# powerSupply.net
KiCad netlist of a schematic drawn in Altium Designer
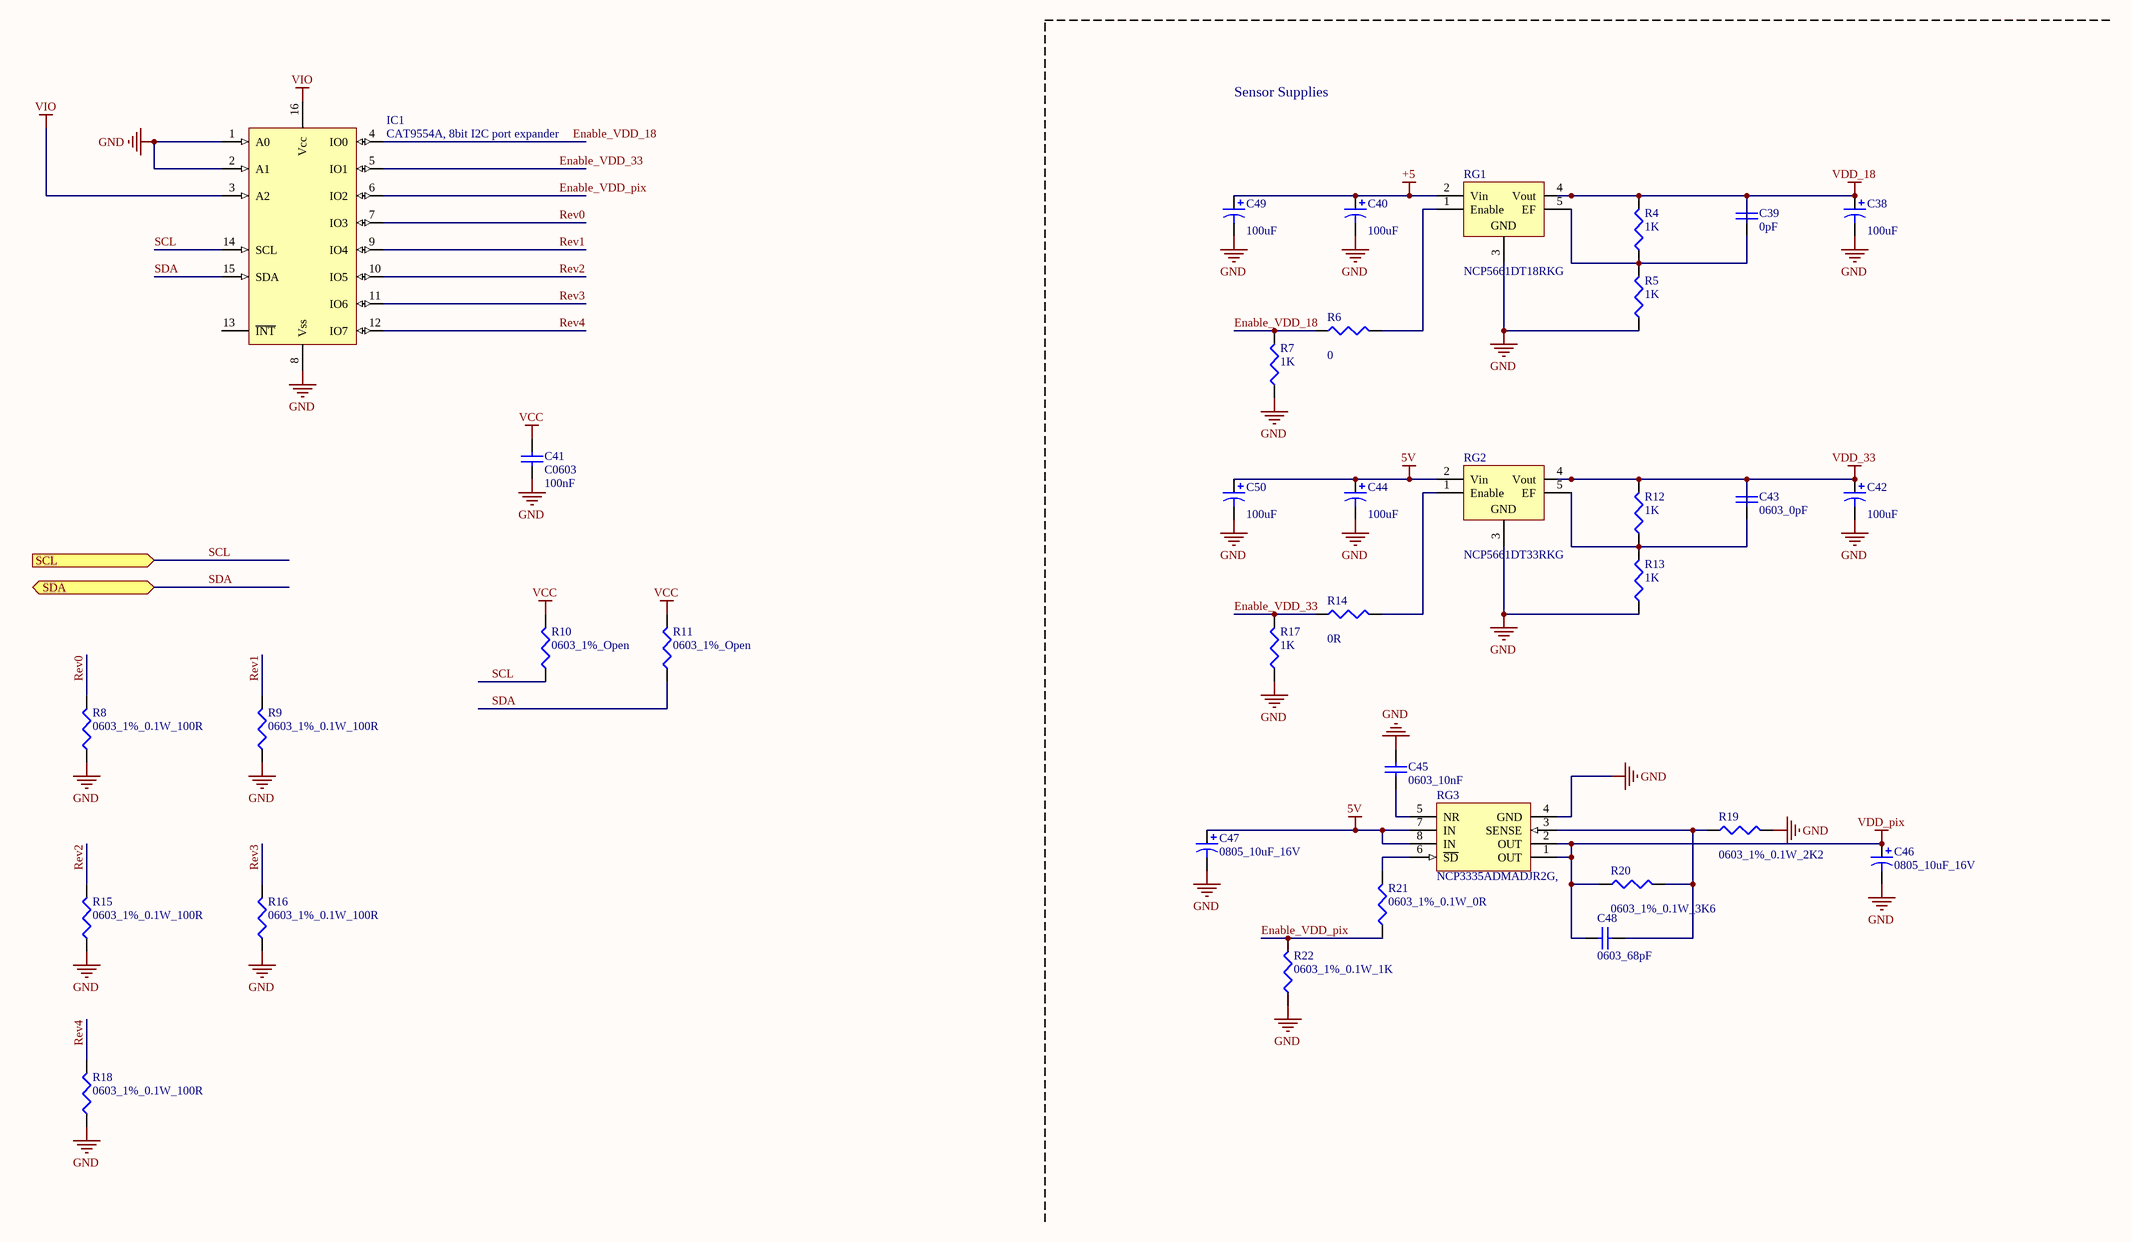
[diagram p0: powerSupply.SchDoc]

(export (version "E")
  (design (tool "Eeschema 10.0.6"))
  (components
    (comp (ref "C38")
      (value "100uF")
      (footprint "CC3225-1210")
      (description "Solid Tantalum Chip Capacitor, Standard T494 Series - Low ESR, Industrial Grade")
      (fields (field (name "Comment") "T494B") (field (name "PUBLISHER") "Altium Limited"))
      (libsource (lib "KEMET Chip Capacitor") (part "T494B"))
    )
    (comp (ref "C39")
      (value "0pF")
      (footprint "0603")
      (description "Ceramic Chip Capacitor - Standard")
      (fields (field (name "Comment") "C0603") (field (name "PUBLISHER") "Altium Limited"))
      (libsource (lib "KEMET Chip Capacitor") (part "C0603"))
    )
    (comp (ref "C40")
      (value "100uF")
      (footprint "CC3225-1210")
      (description "Solid Tantalum Chip Capacitor, Standard T494 Series - Low ESR, Industrial Grade")
      (fields (field (name "Comment") "T494B") (field (name "PUBLISHER") "Altium Limited"))
      (libsource (lib "KEMET Chip Capacitor") (part "T494B"))
    )
    (comp (ref "C41")
      (value "C0603")
      (footprint "0603")
      (description "Ceramic Chip Capacitor - Standard")
      (fields (field (name "ALTIUM_VALUE") "100nF") (field (name "PUBLISHER") "Altium Limited"))
      (libsource (lib "KEMET Chip Capacitor") (part "C0603"))
    )
    (comp (ref "C42")
      (value "100uF")
      (footprint "CC3225-1210")
      (description "Solid Tantalum Chip Capacitor, Standard T494 Series - Low ESR, Industrial Grade")
      (fields (field (name "Comment") "T494B") (field (name "PUBLISHER") "Altium Limited"))
      (libsource (lib "KEMET Chip Capacitor") (part "T494B"))
    )
    (comp (ref "C43")
      (value "0603_0pF")
      (footprint "0603")
      (description "Ceramic Chip Capacitor - Standard")
      (fields (field (name "Comment") "C0603") (field (name "PUBLISHER") "Altium Limited"))
      (libsource (lib "KEMET Chip Capacitor") (part "C0603"))
    )
    (comp (ref "C44")
      (value "100uF")
      (footprint "CC3225-1210")
      (description "Solid Tantalum Chip Capacitor, Standard T494 Series - Low ESR, Industrial Grade")
      (fields (field (name "Comment") "T494B") (field (name "PUBLISHER") "Altium Limited"))
      (libsource (lib "KEMET Chip Capacitor") (part "T494B"))
    )
    (comp (ref "C45")
      (value "0603_10nF")
      (footprint "0603")
      (description "Ceramic Chip Capacitor - Standard")
      (fields (field (name "Comment") "C0603") (field (name "PUBLISHER") "Altium Limited"))
      (libsource (lib "KEMET Chip Capacitor") (part "C0603"))
    )
    (comp (ref "C46")
      (value "0805_10uF_16V")
      (footprint "C0805")
      (description "Polarized Capacitor (Surface Mount)")
      (fields (field (name "Comment") "Cap Pol3") (field (name "PUBLISHER") "Altium Limited"))
      (libsource (lib "Miscellaneous Devices") (part "Cap Pol3"))
    )
    (comp (ref "C47")
      (value "0805_10uF_16V")
      (footprint "C0805")
      (description "Polarized Capacitor (Surface Mount)")
      (fields (field (name "Comment") "Cap Pol3") (field (name "PUBLISHER") "Altium Limited"))
      (libsource (lib "Miscellaneous Devices") (part "Cap Pol3"))
    )
    (comp (ref "C48")
      (value "0603_68pF")
      (footprint "0603")
      (description "Ceramic Chip Capacitor - Standard")
      (fields (field (name "Comment") "C0603") (field (name "PUBLISHER") "Altium Limited"))
      (libsource (lib "KEMET Chip Capacitor") (part "C0603"))
    )
    (comp (ref "C49")
      (value "100uF")
      (footprint "CC3225-1210")
      (description "Solid Tantalum Chip Capacitor, Standard T494 Series - Low ESR, Industrial Grade")
      (fields (field (name "Comment") "T494B") (field (name "PUBLISHER") "Altium Limited"))
      (libsource (lib "KEMET Chip Capacitor") (part "T494B"))
    )
    (comp (ref "C50")
      (value "100uF")
      (footprint "CC3225-1210")
      (description "Solid Tantalum Chip Capacitor, Standard T494 Series - Low ESR, Industrial Grade")
      (fields (field (name "Comment") "T494B") (field (name "PUBLISHER") "Altium Limited"))
      (libsource (lib "KEMET Chip Capacitor") (part "T494B"))
    )
    (comp (ref "IC1")
      (value "CAT9554A, 8bit I2C port expander")
      (footprint "TSSOP16_N")
      (description "8bit I2C port expander")
      (fields (field (name "PUBLISHER") "Altium Limited"))
      (libsource (lib "camera") (part "CAT9554A"))
    )
    (comp (ref "R4")
      (value "1K")
      (footprint "J1-0603")
      (description "Resistor")
      (fields (field (name "Comment") "Res3") (field (name "PUBLISHER") "Altium Limited"))
      (libsource (lib "Miscellaneous Devices") (part "Res3"))
    )
    (comp (ref "R5")
      (value "1K")
      (footprint "J1-0603")
      (description "Resistor")
      (fields (field (name "Comment") "Res3") (field (name "PUBLISHER") "Altium Limited"))
      (libsource (lib "Miscellaneous Devices") (part "Res3"))
    )
    (comp (ref "R6")
      (value "0")
      (footprint "J1-0603")
      (description "Resistor")
      (fields (field (name "Comment") "Res3") (field (name "PUBLISHER") "Altium Limited"))
      (libsource (lib "Miscellaneous Devices") (part "Res3"))
    )
    (comp (ref "R7")
      (value "1K")
      (footprint "J1-0603")
      (description "Resistor")
      (fields (field (name "Comment") "Res3") (field (name "PUBLISHER") "Altium Limited"))
      (libsource (lib "Miscellaneous Devices") (part "Res3"))
    )
    (comp (ref "R8")
      (value "0603_1%_0.1W_100R")
      (footprint "J1-0603")
      (description "Resistor")
      (fields (field (name "Comment") "Res3") (field (name "PUBLISHER") "Altium Limited"))
      (libsource (lib "Miscellaneous Devices") (part "Res3"))
    )
    (comp (ref "R9")
      (value "0603_1%_0.1W_100R")
      (footprint "J1-0603")
      (description "Resistor")
      (fields (field (name "Comment") "Res3") (field (name "PUBLISHER") "Altium Limited"))
      (libsource (lib "Miscellaneous Devices") (part "Res3"))
    )
    (comp (ref "R10")
      (value "0603_1%_Open")
      (footprint "J1-0603")
      (description "Resistor")
      (fields (field (name "Comment") "Res3") (field (name "PUBLISHER") "Altium Limited"))
      (libsource (lib "Miscellaneous Devices") (part "Res3"))
    )
    (comp (ref "R11")
      (value "0603_1%_Open")
      (footprint "J1-0603")
      (description "Resistor")
      (fields (field (name "Comment") "Res3") (field (name "PUBLISHER") "Altium Limited"))
      (libsource (lib "Miscellaneous Devices") (part "Res3"))
    )
    (comp (ref "R12")
      (value "1K")
      (footprint "J1-0603")
      (description "Resistor")
      (fields (field (name "Comment") "Res3") (field (name "PUBLISHER") "Altium Limited"))
      (libsource (lib "Miscellaneous Devices") (part "Res3"))
    )
    (comp (ref "R13")
      (value "1K")
      (footprint "J1-0603")
      (description "Resistor")
      (fields (field (name "Comment") "Res3") (field (name "PUBLISHER") "Altium Limited"))
      (libsource (lib "Miscellaneous Devices") (part "Res3"))
    )
    (comp (ref "R14")
      (value "0R")
      (footprint "J1-0603")
      (description "Resistor")
      (fields (field (name "Comment") "Res3") (field (name "PUBLISHER") "Altium Limited"))
      (libsource (lib "Miscellaneous Devices") (part "Res3"))
    )
    (comp (ref "R15")
      (value "0603_1%_0.1W_100R")
      (footprint "J1-0603")
      (description "Resistor")
      (fields (field (name "Comment") "Res3") (field (name "PUBLISHER") "Altium Limited"))
      (libsource (lib "Miscellaneous Devices") (part "Res3"))
    )
    (comp (ref "R16")
      (value "0603_1%_0.1W_100R")
      (footprint "J1-0603")
      (description "Resistor")
      (fields (field (name "Comment") "Res3") (field (name "PUBLISHER") "Altium Limited"))
      (libsource (lib "Miscellaneous Devices") (part "Res3"))
    )
    (comp (ref "R17")
      (value "1K")
      (footprint "J1-0603")
      (description "Resistor")
      (fields (field (name "Comment") "Res3") (field (name "PUBLISHER") "Altium Limited"))
      (libsource (lib "Miscellaneous Devices") (part "Res3"))
    )
    (comp (ref "R18")
      (value "0603_1%_0.1W_100R")
      (footprint "J1-0603")
      (description "Resistor")
      (fields (field (name "Comment") "Res3") (field (name "PUBLISHER") "Altium Limited"))
      (libsource (lib "Miscellaneous Devices") (part "Res3"))
    )
    (comp (ref "R19")
      (value "0603_1%_0.1W_2K2")
      (footprint "J1-0603")
      (description "Resistor")
      (fields (field (name "Comment") "Res3") (field (name "PUBLISHER") "Altium Limited"))
      (libsource (lib "Miscellaneous Devices") (part "Res3"))
    )
    (comp (ref "R20")
      (value "0603_1%_0.1W_3K6")
      (footprint "J1-0603")
      (description "Resistor")
      (fields (field (name "Comment") "Res3") (field (name "PUBLISHER") "Altium Limited"))
      (libsource (lib "Miscellaneous Devices") (part "Res3"))
    )
    (comp (ref "R21")
      (value "0603_1%_0.1W_0R")
      (footprint "J1-0603")
      (description "Resistor")
      (fields (field (name "Comment") "Res3") (field (name "PUBLISHER") "Altium Limited"))
      (libsource (lib "Miscellaneous Devices") (part "Res3"))
    )
    (comp (ref "R22")
      (value "0603_1%_0.1W_1K")
      (footprint "J1-0603")
      (description "Resistor")
      (fields (field (name "Comment") "Res3") (field (name "PUBLISHER") "Altium Limited"))
      (libsource (lib "Miscellaneous Devices") (part "Res3"))
    )
    (comp (ref "RG1")
      (value "NCP5661DT18RKG")
      (footprint "D-PAK SIP-G5/Z10.9")
      (description "Low Dropout Voltage Regulator")
      (fields (field (name "PUBLISHER") "Altium Limited"))
      (libsource (lib "camera") (part "NCP5661"))
    )
    (comp (ref "RG2")
      (value "NCP5661DT33RKG")
      (footprint "D-PAK SIP-G5/Z10.9")
      (description "Low Dropout Voltage Regulator")
      (fields (field (name "PUBLISHER") "Altium Limited"))
      (libsource (lib "camera") (part "NCP5661"))
    )
    (comp (ref "RG3")
      (value "NCP3335ADMADJR2G,")
      (footprint "ONSC-MICRO-8-846A-02_H_V")
      (description "NCP3335ADMADJR2G, ADJ Ultra High Accuracy, Low Iq, 500 mA Low Dropout Regulator")
      (fields (field (name "PUBLISHER") "Altium Limited"))
      (libsource (lib "camera") (part "NCP3335"))
    )
  )
  (nets
    (net (code "1") (name "+5") (class "Default")
      (node (ref "C40") (pin "1") (pinfunction "1_1") (pintype "passive"))
      (node (ref "C49") (pin "1") (pinfunction "1_1") (pintype "passive"))
      (node (ref "RG1") (pin "2") (pinfunction "Vin_2") (pintype "power_in"))
    )
    (net (code "2") (name "/Enable_VDD_18") (class "Default")
      (node (ref "IC1") (pin "4") (pinfunction "IO0_4") (pintype "bidirectional"))
      (node (ref "R6") (pin "1") (pinfunction "1_1") (pintype "passive"))
      (node (ref "R7") (pin "2") (pinfunction "2_2") (pintype "passive"))
    )
    (net (code "3") (name "/Enable_VDD_33") (class "Default")
      (node (ref "IC1") (pin "5") (pinfunction "IO1_5") (pintype "bidirectional"))
      (node (ref "R14") (pin "1") (pinfunction "1_1") (pintype "passive"))
      (node (ref "R17") (pin "2") (pinfunction "2_2") (pintype "passive"))
    )
    (net (code "4") (name "/Enable_VDD_pix") (class "Default")
      (node (ref "IC1") (pin "6") (pinfunction "IO2_6") (pintype "bidirectional"))
      (node (ref "R21") (pin "1") (pinfunction "1_1") (pintype "passive"))
      (node (ref "R22") (pin "2") (pinfunction "2_2") (pintype "passive"))
    )
    (net (code "5") (name "/Rev0") (class "Default")
      (node (ref "IC1") (pin "7") (pinfunction "IO3_7") (pintype "bidirectional"))
      (node (ref "R8") (pin "2") (pinfunction "2_2") (pintype "passive"))
    )
    (net (code "6") (name "/Rev1") (class "Default")
      (node (ref "IC1") (pin "9") (pinfunction "IO4_9") (pintype "bidirectional"))
      (node (ref "R9") (pin "2") (pinfunction "2_2") (pintype "passive"))
    )
    (net (code "7") (name "/Rev2") (class "Default")
      (node (ref "IC1") (pin "10") (pinfunction "IO5_10") (pintype "bidirectional"))
      (node (ref "R15") (pin "2") (pinfunction "2_2") (pintype "passive"))
    )
    (net (code "8") (name "/Rev3") (class "Default")
      (node (ref "IC1") (pin "11") (pinfunction "IO6_11") (pintype "bidirectional"))
      (node (ref "R16") (pin "2") (pinfunction "2_2") (pintype "passive"))
    )
    (net (code "9") (name "/Rev4") (class "Default")
      (node (ref "IC1") (pin "12") (pinfunction "IO7_12") (pintype "bidirectional"))
      (node (ref "R18") (pin "2") (pinfunction "2_2") (pintype "passive"))
    )
    (net (code "10") (name "/SCL") (class "Default")
      (node (ref "IC1") (pin "14") (pinfunction "SCL_14") (pintype "input"))
      (node (ref "R10") (pin "1") (pinfunction "1_1") (pintype "passive"))
    )
    (net (code "11") (name "/SDA") (class "Default")
      (node (ref "IC1") (pin "15") (pinfunction "SDA_15") (pintype "input"))
      (node (ref "R11") (pin "1") (pinfunction "1_1") (pintype "passive"))
    )
    (net (code "12") (name "5V") (class "Default")
      (node (ref "C44") (pin "1") (pinfunction "1_1") (pintype "passive"))
      (node (ref "C47") (pin "1") (pinfunction "1_1") (pintype "passive"))
      (node (ref "C50") (pin "1") (pinfunction "1_1") (pintype "passive"))
      (node (ref "RG2") (pin "2") (pinfunction "Vin_2") (pintype "power_in"))
      (node (ref "RG3") (pin "7") (pinfunction "IN_7") (pintype "passive"))
      (node (ref "RG3") (pin "8") (pinfunction "IN_8") (pintype "passive"))
    )
    (net (code "13") (name "GND") (class "Default")
      (node (ref "C38") (pin "2") (pinfunction "2_2") (pintype "passive"))
      (node (ref "C40") (pin "2") (pinfunction "2_2") (pintype "passive"))
      (node (ref "C41") (pin "1") (pinfunction "1_1") (pintype "passive"))
      (node (ref "C42") (pin "2") (pinfunction "2_2") (pintype "passive"))
      (node (ref "C44") (pin "2") (pinfunction "2_2") (pintype "passive"))
      (node (ref "C45") (pin "2") (pinfunction "2_2") (pintype "passive"))
      (node (ref "C46") (pin "2") (pinfunction "2_2") (pintype "passive"))
      (node (ref "C47") (pin "2") (pinfunction "2_2") (pintype "passive"))
      (node (ref "C49") (pin "2") (pinfunction "2_2") (pintype "passive"))
      (node (ref "C50") (pin "2") (pinfunction "2_2") (pintype "passive"))
      (node (ref "IC1") (pin "1") (pinfunction "A0_1") (pintype "input"))
      (node (ref "IC1") (pin "2") (pinfunction "A1_2") (pintype "input"))
      (node (ref "IC1") (pin "8") (pinfunction "Vss_8") (pintype "passive"))
      (node (ref "R13") (pin "1") (pinfunction "1_1") (pintype "passive"))
      (node (ref "R15") (pin "1") (pinfunction "1_1") (pintype "passive"))
      (node (ref "R16") (pin "1") (pinfunction "1_1") (pintype "passive"))
      (node (ref "R17") (pin "1") (pinfunction "1_1") (pintype "passive"))
      (node (ref "R18") (pin "1") (pinfunction "1_1") (pintype "passive"))
      (node (ref "R19") (pin "2") (pinfunction "2_2") (pintype "passive"))
      (node (ref "R22") (pin "1") (pinfunction "1_1") (pintype "passive"))
      (node (ref "R5") (pin "1") (pinfunction "1_1") (pintype "passive"))
      (node (ref "R7") (pin "1") (pinfunction "1_1") (pintype "passive"))
      (node (ref "R8") (pin "1") (pinfunction "1_1") (pintype "passive"))
      (node (ref "R9") (pin "1") (pinfunction "1_1") (pintype "passive"))
      (node (ref "RG1") (pin "3") (pinfunction "GND_3") (pintype "power_in"))
      (node (ref "RG2") (pin "3") (pinfunction "GND_3") (pintype "power_in"))
      (node (ref "RG3") (pin "4") (pinfunction "GND_4") (pintype "power_in"))
    )
    (net (code "14") (name "Net-(RG1-EF)") (class "Default")
      (node (ref "C39") (pin "1") (pinfunction "1_1") (pintype "passive"))
      (node (ref "R4") (pin "1") (pinfunction "1_1") (pintype "passive"))
      (node (ref "R5") (pin "2") (pinfunction "2_2") (pintype "passive"))
      (node (ref "RG1") (pin "5") (pinfunction "EF_5") (pintype "power_in"))
    )
    (net (code "15") (name "Net-(RG1-Enable)") (class "Default")
      (node (ref "R6") (pin "2") (pinfunction "2_2") (pintype "passive"))
      (node (ref "RG1") (pin "1") (pinfunction "Enable_1") (pintype "power_in"))
    )
    (net (code "16") (name "Net-(RG2-EF)") (class "Default")
      (node (ref "C43") (pin "1") (pinfunction "1_1") (pintype "passive"))
      (node (ref "R12") (pin "1") (pinfunction "1_1") (pintype "passive"))
      (node (ref "R13") (pin "2") (pinfunction "2_2") (pintype "passive"))
      (node (ref "RG2") (pin "5") (pinfunction "EF_5") (pintype "power_in"))
    )
    (net (code "17") (name "Net-(RG2-Enable)") (class "Default")
      (node (ref "R14") (pin "2") (pinfunction "2_2") (pintype "passive"))
      (node (ref "RG2") (pin "1") (pinfunction "Enable_1") (pintype "power_in"))
    )
    (net (code "18") (name "Net-(RG3-NR)") (class "Default")
      (node (ref "C45") (pin "1") (pinfunction "1_1") (pintype "passive"))
      (node (ref "RG3") (pin "5") (pinfunction "NR_5") (pintype "passive"))
    )
    (net (code "19") (name "Net-(RG3-SENSE)") (class "Default")
      (node (ref "C48") (pin "2") (pinfunction "2_2") (pintype "passive"))
      (node (ref "R19") (pin "1") (pinfunction "1_1") (pintype "passive"))
      (node (ref "R20") (pin "2") (pinfunction "2_2") (pintype "passive"))
      (node (ref "RG3") (pin "3") (pinfunction "SENSE_3") (pintype "input"))
    )
    (net (code "20") (name "Net-(RG3-~{SD})") (class "Default")
      (node (ref "R21") (pin "2") (pinfunction "2_2") (pintype "passive"))
      (node (ref "RG3") (pin "6") (pinfunction "~{SD}_6") (pintype "input"))
    )
    (net (code "21") (name "VCC") (class "Default")
      (node (ref "C41") (pin "2") (pinfunction "2_2") (pintype "passive"))
      (node (ref "R10") (pin "2") (pinfunction "2_2") (pintype "passive"))
      (node (ref "R11") (pin "2") (pinfunction "2_2") (pintype "passive"))
    )
    (net (code "22") (name "VDD_18") (class "Default")
      (node (ref "C38") (pin "1") (pinfunction "1_1") (pintype "passive"))
      (node (ref "C39") (pin "2") (pinfunction "2_2") (pintype "passive"))
      (node (ref "R4") (pin "2") (pinfunction "2_2") (pintype "passive"))
      (node (ref "RG1") (pin "4") (pinfunction "Vout_4") (pintype "power_in"))
    )
    (net (code "23") (name "VDD_33") (class "Default")
      (node (ref "C42") (pin "1") (pinfunction "1_1") (pintype "passive"))
      (node (ref "C43") (pin "2") (pinfunction "2_2") (pintype "passive"))
      (node (ref "R12") (pin "2") (pinfunction "2_2") (pintype "passive"))
      (node (ref "RG2") (pin "4") (pinfunction "Vout_4") (pintype "power_in"))
    )
    (net (code "24") (name "VDD_pix") (class "Default")
      (node (ref "C46") (pin "1") (pinfunction "1_1") (pintype "passive"))
      (node (ref "C48") (pin "1") (pinfunction "1_1") (pintype "passive"))
      (node (ref "R20") (pin "1") (pinfunction "1_1") (pintype "passive"))
      (node (ref "RG3") (pin "1") (pinfunction "OUT_1") (pintype "passive"))
      (node (ref "RG3") (pin "2") (pinfunction "OUT_2") (pintype "passive"))
    )
    (net (code "25") (name "VIO") (class "Default")
      (node (ref "IC1") (pin "16") (pinfunction "Vcc_16") (pintype "power_in"))
      (node (ref "IC1") (pin "3") (pinfunction "A2_3") (pintype "input"))
    )
    (net (code "26") (name "unconnected-(IC1-~{INT}-Pad13)") (class "Default")
      (node (ref "IC1") (pin "13") (pinfunction "~{INT}_13") (pintype "passive"))
    )
  )
)
